# tinybridge-12mbps.net
KiCad netlist of a schematic drawn in EAGLE
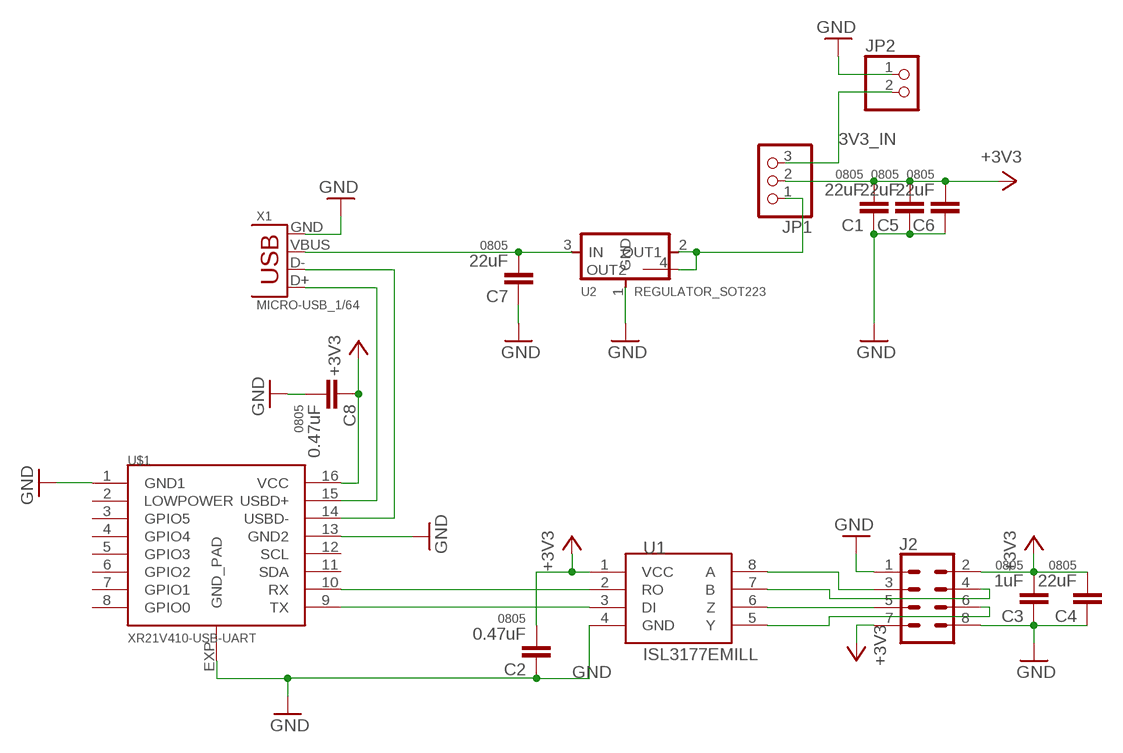
[diagram p0: schematic, sheet 1]

(export (version "E")
  (design (tool "Eeschema 10.0.6"))
  (components
    (comp (ref "C1")
      (value "22uF")
      (footprint "eagle-import:0805")
      (libsource (lib "eagle-import") (part "CAP0805"))
    )
    (comp (ref "C2")
      (value "0.47uF")
      (footprint "eagle-import:0805")
      (libsource (lib "eagle-import") (part "CAP0805"))
    )
    (comp (ref "C3")
      (value "1uF")
      (footprint "eagle-import:0805")
      (libsource (lib "eagle-import") (part "CAP0805"))
    )
    (comp (ref "C4")
      (value "22uF")
      (footprint "eagle-import:0805")
      (libsource (lib "eagle-import") (part "CAP0805"))
    )
    (comp (ref "C5")
      (value "22uF")
      (footprint "eagle-import:0805")
      (libsource (lib "eagle-import") (part "CAP0805"))
    )
    (comp (ref "C6")
      (value "22uF")
      (footprint "eagle-import:0805")
      (libsource (lib "eagle-import") (part "CAP0805"))
    )
    (comp (ref "C7")
      (value "22uF")
      (footprint "eagle-import:0805")
      (libsource (lib "eagle-import") (part "CAP0805"))
    )
    (comp (ref "C8")
      (value "0.47uF")
      (footprint "eagle-import:0805")
      (libsource (lib "eagle-import") (part "CAP0805"))
    )
    (comp (ref "J2")
      (value "CONN_04X2SHROUDED-SQUISH")
      (footprint "eagle-import:2X4-SHROUDED-SQUISH")
      (libsource (lib "eagle-import") (part "CONN_04X2SHROUDED-SQUISH"))
    )
    (comp (ref "JP1")
      (value "PINHD-1X3")
      (footprint "eagle-import:1X03")
      (libsource (lib "eagle-import") (part "PINHD-1X3"))
    )
    (comp (ref "JP2")
      (value "PINHD-1X2")
      (footprint "eagle-import:1X02")
      (libsource (lib "eagle-import") (part "PINHD-1X2"))
    )
    (comp (ref "U$1")
      (value "XR21V410-USB-UART")
      (footprint "eagle-import:QFN-16-3X3-1-100")
      (libsource (lib "eagle-import") (part "XR21V410-USB-UART"))
    )
    (comp (ref "U1")
      (value "ISL3177EMILL")
      (footprint "eagle-import:MSOP8-8MILPADS")
      (libsource (lib "eagle-import") (part "ISL3177EMILL"))
    )
    (comp (ref "U2")
      (value "REGULATOR_SOT223")
      (footprint "eagle-import:SOT223")
      (libsource (lib "eagle-import") (part "REGULATOR_SOT223"))
    )
    (comp (ref "X1")
      (value "MICRO-USB_1/64")
      (footprint "eagle-import:DX4R005HJ5_64")
      (libsource (lib "eagle-import") (part "MICRO-USB_1/64"))
    )
  )
  (nets
    (net (code "1") (name "+3V3") (class "Default")
      (node (ref "C1") (pin "2") (pinfunction "2_2") (pintype "passive"))
      (node (ref "C2") (pin "2") (pinfunction "2_2") (pintype "passive"))
      (node (ref "C3") (pin "2") (pinfunction "2_2") (pintype "passive"))
      (node (ref "C4") (pin "2") (pinfunction "2_2") (pintype "passive"))
      (node (ref "C5") (pin "2") (pinfunction "2_2") (pintype "passive"))
      (node (ref "C6") (pin "2") (pinfunction "2_2") (pintype "passive"))
      (node (ref "C8") (pin "1") (pinfunction "1_1") (pintype "passive"))
      (node (ref "J2") (pin "2") (pinfunction "2_2") (pintype "passive"))
      (node (ref "J2") (pin "7") (pinfunction "7_7") (pintype "passive"))
      (node (ref "JP1") (pin "2") (pinfunction "2_2") (pintype "passive"))
      (node (ref "U$1") (pin "16") (pinfunction "VCC_16") (pintype "bidirectional"))
      (node (ref "U1") (pin "1") (pinfunction "VCC_1") (pintype "bidirectional"))
    )
    (net (code "2") (name "/3V3_IN") (class "Default")
      (node (ref "JP1") (pin "3") (pinfunction "3_3") (pintype "passive"))
      (node (ref "JP2") (pin "2") (pinfunction "2_2") (pintype "passive"))
    )
    (net (code "3") (name "GND") (class "Default")
      (node (ref "C1") (pin "1") (pinfunction "1_1") (pintype "passive"))
      (node (ref "C2") (pin "1") (pinfunction "1_1") (pintype "passive"))
      (node (ref "C3") (pin "1") (pinfunction "1_1") (pintype "passive"))
      (node (ref "C4") (pin "1") (pinfunction "1_1") (pintype "passive"))
      (node (ref "C5") (pin "1") (pinfunction "1_1") (pintype "passive"))
      (node (ref "C6") (pin "1") (pinfunction "1_1") (pintype "passive"))
      (node (ref "C7") (pin "1") (pinfunction "1_1") (pintype "passive"))
      (node (ref "C8") (pin "2") (pinfunction "2_2") (pintype "passive"))
      (node (ref "J2") (pin "1") (pinfunction "1_1") (pintype "passive"))
      (node (ref "J2") (pin "8") (pinfunction "8_8") (pintype "passive"))
      (node (ref "JP2") (pin "1") (pinfunction "1_1") (pintype "passive"))
      (node (ref "U$1") (pin "1") (pinfunction "GND1_1") (pintype "bidirectional"))
      (node (ref "U$1") (pin "13") (pinfunction "GND2_13") (pintype "bidirectional"))
      (node (ref "U$1") (pin "EXP") (pinfunction "GND_PAD_EXP") (pintype "bidirectional"))
      (node (ref "U1") (pin "4") (pinfunction "GND_4") (pintype "bidirectional"))
      (node (ref "U2") (pin "1") (pinfunction "GND_1") (pintype "bidirectional"))
      (node (ref "X1") (pin "GND") (pinfunction "GND_GND") (pintype "bidirectional"))
    )
    (net (code "4") (name "Net-(U$1-RX)") (class "Default")
      (node (ref "U$1") (pin "10") (pinfunction "RX_10") (pintype "bidirectional"))
      (node (ref "U1") (pin "2") (pinfunction "RO_2") (pintype "bidirectional"))
    )
    (net (code "5") (name "Net-(U$1-TX)") (class "Default")
      (node (ref "U$1") (pin "9") (pinfunction "TX_9") (pintype "bidirectional"))
      (node (ref "U1") (pin "3") (pinfunction "DI_3") (pintype "bidirectional"))
    )
    (net (code "6") (name "Net-(U$1-USBD+)") (class "Default")
      (node (ref "U$1") (pin "15") (pinfunction "USBD+_15") (pintype "bidirectional"))
      (node (ref "X1") (pin "D+") (pinfunction "D+_D+") (pintype "bidirectional"))
    )
    (net (code "7") (name "Net-(U$1-USBD-)") (class "Default")
      (node (ref "U$1") (pin "14") (pinfunction "USBD-_14") (pintype "bidirectional"))
      (node (ref "X1") (pin "D-") (pinfunction "D-_D-") (pintype "bidirectional"))
    )
    (net (code "8") (name "Net-(U1-A)") (class "Default")
      (node (ref "J2") (pin "3") (pinfunction "3_3") (pintype "passive"))
      (node (ref "U1") (pin "8") (pinfunction "A_8") (pintype "bidirectional"))
    )
    (net (code "9") (name "Net-(U1-B)") (class "Default")
      (node (ref "J2") (pin "4") (pinfunction "4_4") (pintype "passive"))
      (node (ref "U1") (pin "7") (pinfunction "B_7") (pintype "bidirectional"))
    )
    (net (code "10") (name "Net-(U1-Y)") (class "Default")
      (node (ref "J2") (pin "6") (pinfunction "6_6") (pintype "passive"))
      (node (ref "U1") (pin "5") (pinfunction "Y_5") (pintype "bidirectional"))
    )
    (net (code "11") (name "Net-(U1-Z)") (class "Default")
      (node (ref "J2") (pin "5") (pinfunction "5_5") (pintype "passive"))
      (node (ref "U1") (pin "6") (pinfunction "Z_6") (pintype "bidirectional"))
    )
    (net (code "12") (name "Net-(U2-IN)") (class "Default")
      (node (ref "C7") (pin "2") (pinfunction "2_2") (pintype "passive"))
      (node (ref "U2") (pin "3") (pinfunction "IN_3") (pintype "bidirectional"))
      (node (ref "X1") (pin "VBUS") (pinfunction "VBUS_VBUS") (pintype "bidirectional"))
    )
    (net (code "13") (name "Net-(U2-OUT1)") (class "Default")
      (node (ref "JP1") (pin "1") (pinfunction "1_1") (pintype "passive"))
      (node (ref "U2") (pin "2") (pinfunction "OUT1_2") (pintype "bidirectional"))
      (node (ref "U2") (pin "4") (pinfunction "OUT2_4") (pintype "bidirectional"))
    )
    (net (code "14") (name "unconnected-(U$1-GPIO0-Pad8)") (class "Default")
      (node (ref "U$1") (pin "8") (pinfunction "GPIO0_8") (pintype "bidirectional"))
    )
    (net (code "15") (name "unconnected-(U$1-GPIO1-Pad7)") (class "Default")
      (node (ref "U$1") (pin "7") (pinfunction "GPIO1_7") (pintype "bidirectional"))
    )
    (net (code "16") (name "unconnected-(U$1-GPIO2-Pad6)") (class "Default")
      (node (ref "U$1") (pin "6") (pinfunction "GPIO2_6") (pintype "bidirectional"))
    )
    (net (code "17") (name "unconnected-(U$1-GPIO3-Pad5)") (class "Default")
      (node (ref "U$1") (pin "5") (pinfunction "GPIO3_5") (pintype "bidirectional"))
    )
    (net (code "18") (name "unconnected-(U$1-GPIO4-Pad4)") (class "Default")
      (node (ref "U$1") (pin "4") (pinfunction "GPIO4_4") (pintype "bidirectional"))
    )
    (net (code "19") (name "unconnected-(U$1-GPIO5-Pad3)") (class "Default")
      (node (ref "U$1") (pin "3") (pinfunction "GPIO5_3") (pintype "bidirectional"))
    )
    (net (code "20") (name "unconnected-(U$1-LOWPOWER-Pad2)") (class "Default")
      (node (ref "U$1") (pin "2") (pinfunction "LOWPOWER_2") (pintype "bidirectional"))
    )
    (net (code "21") (name "unconnected-(U$1-SCL-Pad12)") (class "Default")
      (node (ref "U$1") (pin "12") (pinfunction "SCL_12") (pintype "bidirectional"))
    )
    (net (code "22") (name "unconnected-(U$1-SDA-Pad11)") (class "Default")
      (node (ref "U$1") (pin "11") (pinfunction "SDA_11") (pintype "bidirectional"))
    )
  )
)
